# Power_Distribution_-_Parking_Brake_Actua.net
KiCad netlist of a schematic drawn in Altium Designer
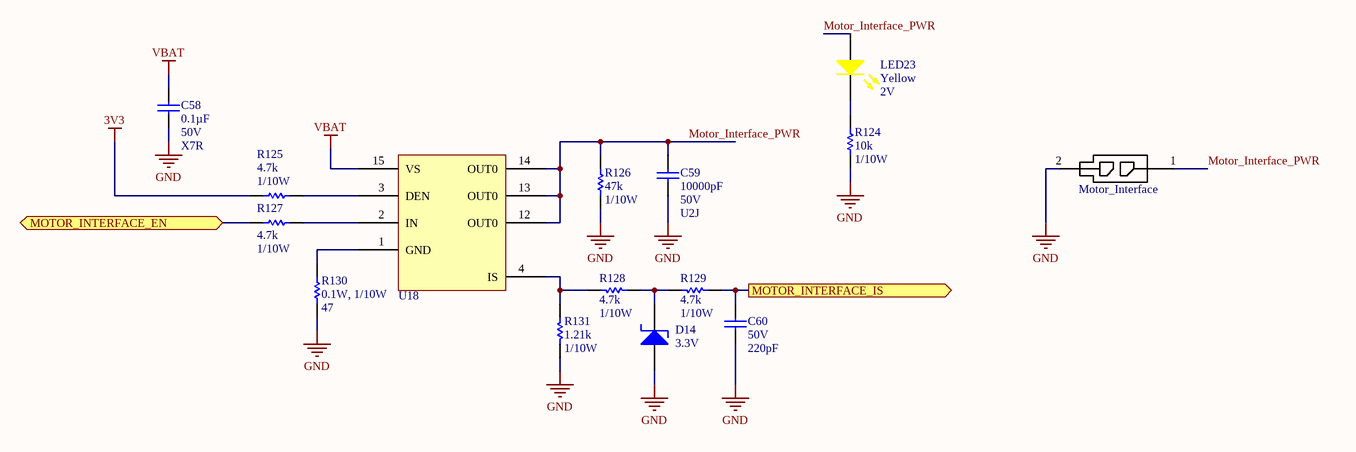
[diagram p0: Power Distribution - Parking Brake Actuator.SchDoc]

(export (version "E")
  (design (tool "Eeschema 10.0.6"))
  (components
    (comp (ref "C58")
      (value "CAP CER 0.1UF 50V 10% X7R 0603")
      (footprint "CAP, 0603")
      (description "0.10µF ±10% 50V Ceramic Capacitor X7R 0603 (1608 Metric)")
      (fields
        (field (name "TOLERANCE") "±10%")
        (field (name "CAPACITANCE") "0.1µF")
        (field (name "VOLTAGE") "50V")
        (field (name "TEMPERATURE COEFFICIENT") "X7R")
      )
      (libsource (lib "Schematic Diagrams") (part "CAP CER 0.1UF 50V 10% X7R 0603"))
    )
    (comp (ref "C59")
      (value "CAP CER 10nF 50V 5% X7R 0603")
      (footprint "CAP, 0603")
      (description "10000pF ±5% 50V Ceramic Capacitor U2J 0603 (1608 Metric)")
      (fields
        (field (name "TOLERANCE") "±5%")
        (field (name "CAPACITANCE") "10000pF")
        (field (name "VOLTAGE") "50V")
        (field (name "TEMPERATURE COEFFICIENT") "U2J")
      )
      (libsource (lib "Schematic Diagrams") (part "CAP CER 10nF 50V 5% X7R 0603"))
    )
    (comp (ref "C60")
      (value "CAP CER 220PF 50V C0G/NP0 0603")
      (footprint "CAP, 0603")
      (description "220pF ±5% 50V Ceramic Capacitor C0G, NP0 0603 (1608 Metric)")
      (fields
        (field (name "MANUFACTURER") "KEMET")
        (field (name "TOLERANCE") "5%")
        (field (name "VOLTAGE RATING") "50V")
        (field (name "CAPACITANCE") "220pF")
      )
      (libsource (lib "Schematic Diagrams") (part "CAP CER 220PF 50V C0G/NP0 0603"))
    )
    (comp (ref "D14")
      (value "DIODE ZENER 3.3V 200MW SOD323")
      (footprint "sod-323")
      (description "Zener Diode 3.3V 200mW ±5% Surface Mount SOD-323")
      (fields (field (name "VOLTAGE") "3.3V"))
      (libsource (lib "Schematic Diagrams") (part "DIODE ZENER 3.3V 200MW SOD323"))
    )
    (comp (ref "LED23")
      (value "LED YELLOW CLEAR 2.1V 0603")
      (footprint "LED_0603")
      (description "Yellow 590nm LED Indication - Discrete 2V 0603 (1608 Metric)")
      (fields
        (field (name "MANUFACTURER") "Wurth Electronics Inc.")
        (field (name "MANUFACTURER PART NUMBER") "150060YS75000")
        (field (name "COLOR") "Yellow")
        (field (name "VOLTAGE - FORWARD (VF) (TYP)") "2V")
      )
      (libsource (lib "Schematic Diagrams") (part "LED YELLOW CLEAR 2.1V 0603"))
    )
    (comp (ref "Motor_Interface")
      (value "CONN 2POS MICRO-FIT 3mm")
      (footprint "CONN, 2POS MICRO-FIT")
      (description "Connector Header Through Hole 2 position")
      (fields (field (name "MANUFACTURER") "Molex") (field (name "MANUFACTURER PART NUMBER") "43045-0227"))
      (libsource (lib "Schematic Diagrams") (part "CONN 2POS MICRO-FIT 3mm"))
    )
    (comp (ref "R124")
      (value "RES 10K OHM 1% 1/10W 0603")
      (footprint "RES, 0603")
      (description "RES SMD 10K OHM 1% 1/10W 0603")
      (fields
        (field (name "TOLERANCE") "±1%")
        (field (name "RESISTANCE") "10k")
        (field (name "POWER") "1/10W")
      )
      (libsource (lib "Schematic Diagrams") (part "RES 10K OHM 1% 1/10W 0603"))
    )
    (comp (ref "R125")
      (value "RES 4.7K OHM 1% 1/10W 0603")
      (footprint "RES, 0603")
      (description "4.7k Ohm ±1% 0.1W, 1/10W Chip Resistor 0603 (1608 Metric) Moisture Resistant Thick Film")
      (fields
        (field (name "TOLERANCE") "±1%")
        (field (name "RESISTANCE (OHMS)") "4.7k")
        (field (name "POWER (WATTS)") "1/10W")
      )
      (libsource (lib "Schematic Diagrams") (part "RES 4.7K OHM 1% 1/10W 0603"))
    )
    (comp (ref "R126")
      (value "RES 47K OHM 1% 1/10W 0603")
      (footprint "RES, 0603")
      (description "47 kOhms ±1% 0.1W, 1/10W Chip Resistor 0603 (1608 Metric) Automotive AEC-Q200 Thick Film")
      (fields
        (field (name "MANUFACTURER") "Panasonic")
        (field (name "MANUFACTURER PART NUMBER") "ERJ3EKF4702V")
        (field (name "RESISTANCE") "47k")
        (field (name "POWER RATING") "1/10W")
      )
      (libsource (lib "Schematic Diagrams") (part "RES 47K OHM 1% 1/10W 0603"))
    )
    (comp (ref "R127")
      (value "RES 4.7K OHM 1% 1/10W 0603")
      (footprint "RES, 0603")
      (description "4.7k Ohm ±1% 0.1W, 1/10W Chip Resistor 0603 (1608 Metric) Moisture Resistant Thick Film")
      (fields
        (field (name "TOLERANCE") "±1%")
        (field (name "RESISTANCE (OHMS)") "4.7k")
        (field (name "POWER (WATTS)") "1/10W")
      )
      (libsource (lib "Schematic Diagrams") (part "RES 4.7K OHM 1% 1/10W 0603"))
    )
    (comp (ref "R128")
      (value "RES 4.7K OHM 1% 1/10W 0603")
      (footprint "RES, 0603")
      (description "4.7k Ohm ±1% 0.1W, 1/10W Chip Resistor 0603 (1608 Metric) Moisture Resistant Thick Film")
      (fields
        (field (name "TOLERANCE") "±1%")
        (field (name "RESISTANCE (OHMS)") "4.7k")
        (field (name "POWER (WATTS)") "1/10W")
      )
      (libsource (lib "Schematic Diagrams") (part "RES 4.7K OHM 1% 1/10W 0603"))
    )
    (comp (ref "R129")
      (value "RES 4.7K OHM 1% 1/10W 0603")
      (footprint "RES, 0603")
      (description "4.7k Ohm ±1% 0.1W, 1/10W Chip Resistor 0603 (1608 Metric) Moisture Resistant Thick Film")
      (fields
        (field (name "TOLERANCE") "±1%")
        (field (name "RESISTANCE (OHMS)") "4.7k")
        (field (name "POWER (WATTS)") "1/10W")
      )
      (libsource (lib "Schematic Diagrams") (part "RES 4.7K OHM 1% 1/10W 0603"))
    )
    (comp (ref "R130")
      (value "RES SMD 47 OHM 1% 1/10W 0603")
      (footprint "RES, 0603")
      (fields
        (field (name "TOLERANCE") "±1%")
        (field (name "POWER (WATTS)") "0.1W, 1/10W")
        (field (name "VALUES") "47")
      )
      (libsource (lib "Schematic Diagrams") (part "RES SMD 47 OHM 1% 1/10W 0603"))
    )
    (comp (ref "R131")
      (value "RES 1.21K OHM 1% 1/10W 0603")
      (footprint "RES, 0603")
      (description "1.21k Ohm ±1% 0.1W, 1/10W Chip Resistor 0603 (1608 Metric) Moisture Resistant Thick Film")
      (fields
        (field (name "TOLERANCE") "±1%")
        (field (name "RESISTANCE") "1.21k")
        (field (name "POWER") "1/10W")
      )
      (libsource (lib "Schematic Diagrams") (part "RES 1.21K OHM 1% 1/10W 0603"))
    )
    (comp (ref "U18")
      (value "IC LOAD SWITCH BTS70401EPA PG-TSDSO-14-22")
      (footprint "IC LOAD SWITCH PG-TSDSO-14-22")
      (description "Power Switch/Driver 1:1 N-Channel 4.5A PG-TSDSO-14-22")
      (fields
        (field (name "MANUFACTURER") "Infineon")
        (field (name "MANUFACTURER PART NUMBER") "BTS70401EPAXUMA1")
      )
      (libsource (lib "Schematic Diagrams") (part "IC LOAD SWITCH BTS70401EPA PG-TSDSO-14-22"))
    )
  )
  (nets
    (net (code "1") (name "/MOTOR_INTERFACE_EN") (class "Default")
      (node (ref "R127") (pin "1") (pinfunction "1_1") (pintype "passive"))
    )
    (net (code "2") (name "/MOTOR_INTERFACE_IS") (class "Default")
      (node (ref "C60") (pin "1") (pinfunction "1_1") (pintype "passive"))
      (node (ref "R129") (pin "1") (pinfunction "1_1") (pintype "passive"))
    )
    (net (code "3") (name "/Motor_Interface_PWR") (class "Default")
      (node (ref "C59") (pin "1") (pinfunction "1_1") (pintype "passive"))
      (node (ref "LED23") (pin "1") (pinfunction "A_1") (pintype "passive"))
      (node (ref "Motor_Interface") (pin "1") (pinfunction "1_1") (pintype "passive"))
      (node (ref "R126") (pin "1") (pinfunction "1_1") (pintype "passive"))
      (node (ref "U18") (pin "12") (pinfunction "OUT0_12") (pintype "passive"))
      (node (ref "U18") (pin "13") (pinfunction "OUT0_13") (pintype "passive"))
      (node (ref "U18") (pin "14") (pinfunction "OUT0_14") (pintype "passive"))
    )
    (net (code "4") (name "3V3") (class "Default")
      (node (ref "R125") (pin "1") (pinfunction "1_1") (pintype "passive"))
    )
    (net (code "5") (name "GND") (class "Default")
      (node (ref "C58") (pin "2") (pinfunction "2_2") (pintype "passive"))
      (node (ref "C59") (pin "2") (pinfunction "2_2") (pintype "passive"))
      (node (ref "C60") (pin "2") (pinfunction "2_2") (pintype "passive"))
      (node (ref "D14") (pin "1") (pinfunction "A_1") (pintype "passive"))
      (node (ref "Motor_Interface") (pin "2") (pinfunction "2_2") (pintype "passive"))
      (node (ref "R124") (pin "2") (pinfunction "2_2") (pintype "passive"))
      (node (ref "R126") (pin "2") (pinfunction "2_2") (pintype "passive"))
      (node (ref "R130") (pin "2") (pinfunction "2_2") (pintype "passive"))
      (node (ref "R131") (pin "2") (pinfunction "2_2") (pintype "passive"))
    )
    (net (code "6") (name "Net-(D14-K)") (class "Default")
      (node (ref "D14") (pin "2") (pinfunction "K_2") (pintype "passive"))
      (node (ref "R128") (pin "1") (pinfunction "1_1") (pintype "passive"))
      (node (ref "R129") (pin "2") (pinfunction "2_2") (pintype "passive"))
    )
    (net (code "7") (name "Net-(LED23-K)") (class "Default")
      (node (ref "LED23") (pin "2") (pinfunction "K_2") (pintype "passive"))
      (node (ref "R124") (pin "1") (pinfunction "1_1") (pintype "passive"))
    )
    (net (code "8") (name "Net-(U18-DEN)") (class "Default")
      (node (ref "R125") (pin "2") (pinfunction "2_2") (pintype "passive"))
      (node (ref "U18") (pin "3") (pinfunction "DEN_3") (pintype "passive"))
    )
    (net (code "9") (name "Net-(U18-GND)") (class "Default")
      (node (ref "R130") (pin "1") (pinfunction "1_1") (pintype "passive"))
      (node (ref "U18") (pin "1") (pinfunction "GND_1") (pintype "passive"))
    )
    (net (code "10") (name "Net-(U18-IN)") (class "Default")
      (node (ref "R127") (pin "2") (pinfunction "2_2") (pintype "passive"))
      (node (ref "U18") (pin "2") (pinfunction "IN_2") (pintype "passive"))
    )
    (net (code "11") (name "Net-(U18-IS)") (class "Default")
      (node (ref "R128") (pin "2") (pinfunction "2_2") (pintype "passive"))
      (node (ref "R131") (pin "1") (pinfunction "1_1") (pintype "passive"))
      (node (ref "U18") (pin "4") (pinfunction "IS_4") (pintype "passive"))
    )
    (net (code "12") (name "VBAT") (class "Default")
      (node (ref "C58") (pin "1") (pinfunction "1_1") (pintype "passive"))
      (node (ref "U18") (pin "15") (pinfunction "VS_15") (pintype "passive"))
    )
  )
)
